# MCU.net
KiCad netlist of a schematic drawn in Altium Designer
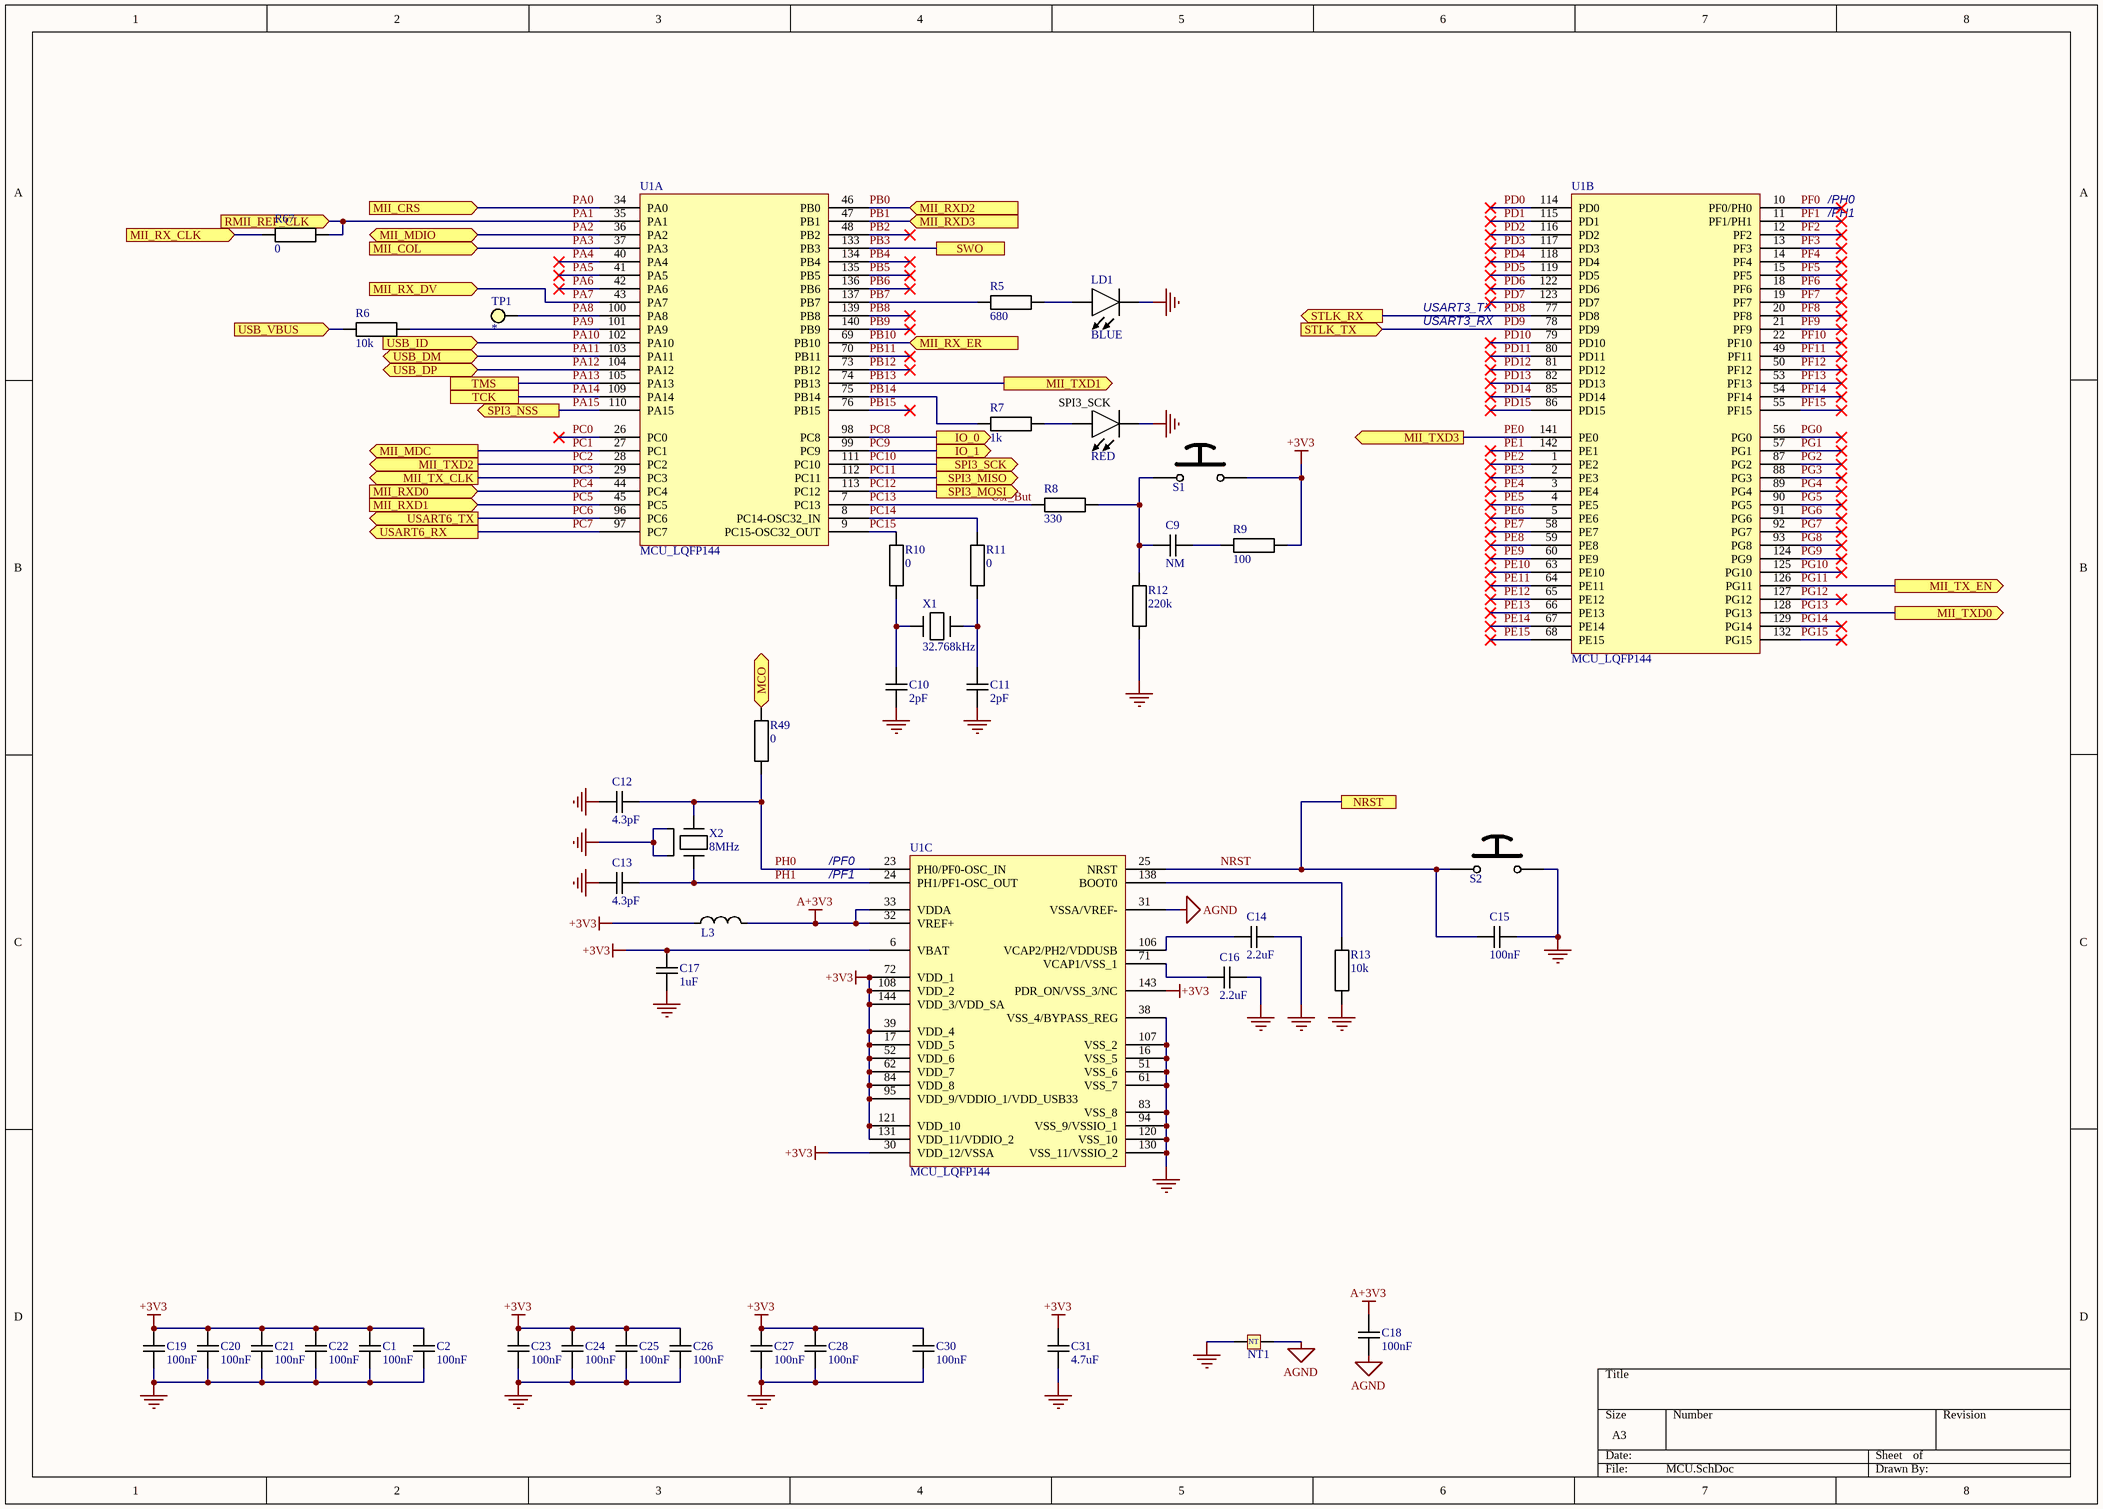
[diagram p0: MCU.SchDoc]

(export (version "E")
  (design (tool "Eeschema 10.0.6"))
  (components
    (comp (ref "C1")
      (value "100nF")
      (footprint "CAPACITOR 1608 REFLOW")
      (description "Capacitor")
      (libsource (lib "Capacitor") (part "Capacitor"))
    )
    (comp (ref "C2")
      (value "100nF")
      (footprint "CAPACITOR 1608 REFLOW")
      (description "Capacitor")
      (libsource (lib "Capacitor") (part "Capacitor"))
    )
    (comp (ref "C9")
      (value "NM")
      (footprint "CAPACITOR 1608 REFLOW")
      (description "Capacitor")
      (libsource (lib "Capacitor") (part "Capacitor"))
    )
    (comp (ref "C10")
      (value "2pF")
      (footprint "CAPACITOR 1608 REFLOW")
      (description "Capacitor")
      (libsource (lib "Capacitor") (part "Capacitor"))
    )
    (comp (ref "C11")
      (value "2pF")
      (footprint "CAPACITOR 1608 REFLOW")
      (description "Capacitor")
      (libsource (lib "Capacitor") (part "Capacitor"))
    )
    (comp (ref "C12")
      (value "4.3pF")
      (footprint "CAPACITOR 1608 REFLOW")
      (description "Capacitor")
      (libsource (lib "Capacitor") (part "Capacitor"))
    )
    (comp (ref "C13")
      (value "4.3pF")
      (footprint "CAPACITOR 1608 REFLOW")
      (description "Capacitor")
      (libsource (lib "Capacitor") (part "Capacitor"))
    )
    (comp (ref "C14")
      (value "2.2uF")
      (footprint "CAPACITOR 1608 REFLOW")
      (description "Capacitor")
      (libsource (lib "Capacitor") (part "Capacitor"))
    )
    (comp (ref "C15")
      (value "100nF")
      (footprint "CAPACITOR 1608 REFLOW")
      (description "Capacitor")
      (libsource (lib "Capacitor") (part "Capacitor"))
    )
    (comp (ref "C16")
      (value "2.2uF")
      (footprint "CAPACITOR 1608 REFLOW")
      (description "Capacitor")
      (libsource (lib "Capacitor") (part "Capacitor"))
    )
    (comp (ref "C17")
      (value "1uF")
      (footprint "CAPACITOR 1608 REFLOW")
      (description "Capacitor")
      (libsource (lib "Capacitor") (part "Capacitor"))
    )
    (comp (ref "C18")
      (value "100nF")
      (footprint "CAPACITOR 1608 REFLOW")
      (description "Capacitor")
      (libsource (lib "Capacitor") (part "Capacitor"))
    )
    (comp (ref "C19")
      (value "100nF")
      (footprint "CAPACITOR 1608 REFLOW")
      (description "Capacitor")
      (libsource (lib "Capacitor") (part "Capacitor"))
    )
    (comp (ref "C20")
      (value "100nF")
      (footprint "CAPACITOR 1608 REFLOW")
      (description "Capacitor")
      (libsource (lib "Capacitor") (part "Capacitor"))
    )
    (comp (ref "C21")
      (value "100nF")
      (footprint "CAPACITOR 1608 REFLOW")
      (description "Capacitor")
      (libsource (lib "Capacitor") (part "Capacitor"))
    )
    (comp (ref "C22")
      (value "100nF")
      (footprint "CAPACITOR 1608 REFLOW")
      (description "Capacitor")
      (libsource (lib "Capacitor") (part "Capacitor"))
    )
    (comp (ref "C23")
      (value "100nF")
      (footprint "CAPACITOR 1608 REFLOW")
      (description "Capacitor")
      (libsource (lib "Capacitor") (part "Capacitor"))
    )
    (comp (ref "C24")
      (value "100nF")
      (footprint "CAPACITOR 1608 REFLOW")
      (description "Capacitor")
      (libsource (lib "Capacitor") (part "Capacitor"))
    )
    (comp (ref "C25")
      (value "100nF")
      (footprint "CAPACITOR 1608 REFLOW")
      (description "Capacitor")
      (libsource (lib "Capacitor") (part "Capacitor"))
    )
    (comp (ref "C26")
      (value "100nF")
      (footprint "CAPACITOR 1608 REFLOW")
      (description "Capacitor")
      (libsource (lib "Capacitor") (part "Capacitor"))
    )
    (comp (ref "C27")
      (value "100nF")
      (footprint "CAPACITOR 1608 REFLOW")
      (description "Capacitor")
      (libsource (lib "Capacitor") (part "Capacitor"))
    )
    (comp (ref "C28")
      (value "100nF")
      (footprint "CAPACITOR 1608 REFLOW")
      (description "Capacitor")
      (libsource (lib "Capacitor") (part "Capacitor"))
    )
    (comp (ref "C30")
      (value "100nF")
      (footprint "CAPACITOR 1608 REFLOW")
      (description "Capacitor")
      (libsource (lib "Capacitor") (part "Capacitor"))
    )
    (comp (ref "C31")
      (value "4.7uF")
      (footprint "CAPACITOR 1608 REFLOW")
      (description "Capacitor")
      (libsource (lib "Capacitor") (part "Capacitor"))
    )
    (comp (ref "L3")
      (value "*")
      (footprint "INDUCTOR 1608 REFLOW")
      (description "Inductor")
      (libsource (lib "Inductor") (part "Inductor"))
    )
    (comp (ref "LD1")
      (value "BLUE")
      (footprint "LED 1608 REFLOW")
      (description "LED generic")
      (libsource (lib "Diode") (part "LED"))
    )
    (comp (ref "LD2")
      (value "RED")
      (footprint "LED 1608 REFLOW")
      (description "LED generic")
      (libsource (lib "Diode") (part "LED"))
    )
    (comp (ref "NT1")
      (value "Net Tie")
      (footprint "NET TIE 1005")
      (description "Connection for 2 different NETNAME")
      (libsource (lib "Jumper") (part "Net Tie"))
    )
    (comp (ref "R5")
      (value "680")
      (footprint "RESISTOR 1608 REFLOW")
      (description "Resistor")
      (libsource (lib "Resistor") (part "Resistor"))
    )
    (comp (ref "R6")
      (value "10k")
      (footprint "RESISTOR 1608 REFLOW")
      (description "Resistor")
      (libsource (lib "Resistor") (part "Resistor"))
    )
    (comp (ref "R7")
      (value "1k")
      (footprint "RESISTOR 1608 REFLOW")
      (description "Resistor")
      (libsource (lib "Resistor") (part "Resistor"))
    )
    (comp (ref "R8")
      (value "330")
      (footprint "RESISTOR 1608 REFLOW")
      (description "Resistor")
      (libsource (lib "Resistor") (part "Resistor"))
    )
    (comp (ref "R9")
      (value "100")
      (footprint "RESISTOR 1608 REFLOW")
      (description "Resistor")
      (libsource (lib "Resistor") (part "Resistor"))
    )
    (comp (ref "R10")
      (value "0")
      (footprint "RESISTOR 1608 REFLOW")
      (description "Resistor")
      (libsource (lib "Resistor") (part "Resistor"))
    )
    (comp (ref "R11")
      (value "0")
      (footprint "RESISTOR 1608 REFLOW")
      (description "Resistor")
      (libsource (lib "Resistor") (part "Resistor"))
    )
    (comp (ref "R12")
      (value "220k")
      (footprint "RESISTOR 1608 REFLOW")
      (description "Resistor")
      (libsource (lib "Resistor") (part "Resistor"))
    )
    (comp (ref "R13")
      (value "10k")
      (footprint "RESISTOR 1608 REFLOW")
      (description "Resistor")
      (libsource (lib "Resistor") (part "Resistor"))
    )
    (comp (ref "R49")
      (value "0")
      (footprint "RESISTOR 1608 REFLOW")
      (description "Resistor")
      (libsource (lib "Resistor") (part "Resistor"))
    )
    (comp (ref "R67")
      (value "0")
      (footprint "RESISTOR 1608 REFLOW")
      (description "Resistor")
      (libsource (lib "Resistor") (part "Resistor"))
    )
    (comp (ref "S1")
      (value "*")
      (footprint "Push Button C2.5X3.0 OMRON B3U-1000P(M)-B")
      (description "Push Button, 2 pins")
      (libsource (lib "Button") (part "Push Button 2Pins"))
    )
    (comp (ref "S2")
      (value "*")
      (footprint "Push Button C2.5X3.0 OMRON B3U-1000P(M)-B")
      (description "Push Button, 2 pins")
      (libsource (lib "Button") (part "Push Button 2Pins"))
    )
    (comp (ref "TP1")
      (value "*")
      (footprint "Pad D0.8")
      (description "Pad")
      (libsource (lib "Testpoint") (part "Pad"))
    )
    (comp (ref "U1")
      (value "MCU_LQFP144")
      (footprint "LQFP144 P0.5 C20.0x20.0 H1.6")
      (libsource (lib "MB1137") (part "MCU_LQFP144"))
    )
    (comp (ref "X1")
      (value "32.768kHz")
      (footprint "Crystal C2.0x1.2 CTS TF20")
      (description "Crystal C2.0x1.2 CTS TF20")
      (libsource (lib "Oscillator") (part "Crystal C2.0x1.2 CTS TF20"))
    )
    (comp (ref "X2")
      (value "8MHz")
      (footprint "Crystal C2.0x1.6 Abracon ABM11W")
      (description "Crystal C2.0x1.6 Abracon ABM11W")
      (libsource (lib "Oscillator") (part "Crystal C2.0x1.6 Abracon ABM11W"))
    )
  )
  (nets
    (net (code "1") (name "+3V3") (class "Default")
      (node (ref "C1") (pin "1") (pinfunction "1_1") (pintype "passive"))
      (node (ref "C17") (pin "2") (pinfunction "2_2") (pintype "passive"))
      (node (ref "C19") (pin "1") (pinfunction "1_1") (pintype "passive"))
      (node (ref "C2") (pin "1") (pinfunction "1_1") (pintype "passive"))
      (node (ref "C20") (pin "1") (pinfunction "1_1") (pintype "passive"))
      (node (ref "C21") (pin "1") (pinfunction "1_1") (pintype "passive"))
      (node (ref "C22") (pin "1") (pinfunction "1_1") (pintype "passive"))
      (node (ref "C23") (pin "1") (pinfunction "1_1") (pintype "passive"))
      (node (ref "C24") (pin "1") (pinfunction "1_1") (pintype "passive"))
      (node (ref "C25") (pin "1") (pinfunction "1_1") (pintype "passive"))
      (node (ref "C26") (pin "1") (pinfunction "1_1") (pintype "passive"))
      (node (ref "C27") (pin "1") (pinfunction "1_1") (pintype "passive"))
      (node (ref "C28") (pin "1") (pinfunction "1_1") (pintype "passive"))
      (node (ref "C30") (pin "1") (pinfunction "1_1") (pintype "passive"))
      (node (ref "C31") (pin "1") (pinfunction "1_1") (pintype "passive"))
      (node (ref "L3") (pin "1") (pinfunction "1_1") (pintype "passive"))
      (node (ref "R9") (pin "2") (pinfunction "2_2") (pintype "passive"))
      (node (ref "S1") (pin "2") (pinfunction "2_2") (pintype "passive"))
      (node (ref "U1") (pin "108") (pinfunction "VDD_2_108") (pintype "passive"))
      (node (ref "U1") (pin "121") (pinfunction "VDD_10_121") (pintype "passive"))
      (node (ref "U1") (pin "131") (pinfunction "VDD_11/VDDIO_2_131") (pintype "passive"))
      (node (ref "U1") (pin "143") (pinfunction "PDR_ON/VSS_3/NC_143") (pintype "passive"))
      (node (ref "U1") (pin "144") (pinfunction "VDD_3/VDD_SA_144") (pintype "passive"))
      (node (ref "U1") (pin "17") (pinfunction "VDD_5_17") (pintype "passive"))
      (node (ref "U1") (pin "30") (pinfunction "VDD_12/VSSA_30") (pintype "passive"))
      (node (ref "U1") (pin "39") (pinfunction "VDD_4_39") (pintype "passive"))
      (node (ref "U1") (pin "52") (pinfunction "VDD_6_52") (pintype "passive"))
      (node (ref "U1") (pin "6") (pinfunction "VBAT_6") (pintype "passive"))
      (node (ref "U1") (pin "62") (pinfunction "VDD_7_62") (pintype "passive"))
      (node (ref "U1") (pin "72") (pinfunction "VDD_1_72") (pintype "passive"))
      (node (ref "U1") (pin "84") (pinfunction "VDD_8_84") (pintype "passive"))
      (node (ref "U1") (pin "95") (pinfunction "VDD_9/VDDIO_1/VDD_USB33_95") (pintype "passive"))
    )
    (net (code "2") (name "/MCO") (class "Default")
      (node (ref "R49") (pin "1") (pinfunction "1_1") (pintype "passive"))
    )
    (net (code "3") (name "/MII_RX_CLK") (class "Default")
      (node (ref "R67") (pin "1") (pinfunction "1_1") (pintype "passive"))
    )
    (net (code "4") (name "/NRST") (class "Default")
      (node (ref "C15") (pin "2") (pinfunction "2_2") (pintype "passive"))
      (node (ref "S2") (pin "1") (pinfunction "1_1") (pintype "passive"))
      (node (ref "U1") (pin "25") (pinfunction "NRST_25") (pintype "passive"))
    )
    (net (code "5") (name "/PA0") (class "Default")
      (node (ref "U1") (pin "34") (pinfunction "PA0_34") (pintype "passive"))
    )
    (net (code "6") (name "/PA1") (class "Default")
      (node (ref "R67") (pin "2") (pinfunction "2_2") (pintype "passive"))
      (node (ref "U1") (pin "35") (pinfunction "PA1_35") (pintype "passive"))
    )
    (net (code "7") (name "/PA2") (class "Default")
      (node (ref "U1") (pin "36") (pinfunction "PA2_36") (pintype "passive"))
    )
    (net (code "8") (name "/PA3") (class "Default")
      (node (ref "U1") (pin "37") (pinfunction "PA3_37") (pintype "passive"))
    )
    (net (code "9") (name "/PA4") (class "Default")
      (node (ref "U1") (pin "40") (pinfunction "PA4_40") (pintype "passive+no_connect"))
    )
    (net (code "10") (name "/PA5") (class "Default")
      (node (ref "U1") (pin "41") (pinfunction "PA5_41") (pintype "passive+no_connect"))
    )
    (net (code "11") (name "/PA6") (class "Default")
      (node (ref "U1") (pin "42") (pinfunction "PA6_42") (pintype "passive+no_connect"))
    )
    (net (code "12") (name "/PA7") (class "Default")
      (node (ref "U1") (pin "43") (pinfunction "PA7_43") (pintype "passive"))
    )
    (net (code "13") (name "/PA8") (class "Default")
      (node (ref "TP1") (pin "1") (pinfunction "1_1") (pintype "passive"))
      (node (ref "U1") (pin "100") (pinfunction "PA8_100") (pintype "passive"))
    )
    (net (code "14") (name "/PA9") (class "Default")
      (node (ref "R6") (pin "1") (pinfunction "1_1") (pintype "passive"))
      (node (ref "U1") (pin "101") (pinfunction "PA9_101") (pintype "passive"))
    )
    (net (code "15") (name "/PA10") (class "Default")
      (node (ref "U1") (pin "102") (pinfunction "PA10_102") (pintype "passive"))
    )
    (net (code "16") (name "/PA11") (class "Default")
      (node (ref "U1") (pin "103") (pinfunction "PA11_103") (pintype "passive"))
    )
    (net (code "17") (name "/PA12") (class "Default")
      (node (ref "U1") (pin "104") (pinfunction "PA12_104") (pintype "passive"))
    )
    (net (code "18") (name "/PA13") (class "Default")
      (node (ref "U1") (pin "105") (pinfunction "PA13_105") (pintype "passive"))
    )
    (net (code "19") (name "/PA14") (class "Default")
      (node (ref "U1") (pin "109") (pinfunction "PA14_109") (pintype "passive"))
    )
    (net (code "20") (name "/PA15") (class "Default")
      (node (ref "U1") (pin "110") (pinfunction "PA15_110") (pintype "passive"))
    )
    (net (code "21") (name "/PB0") (class "Default")
      (node (ref "U1") (pin "46") (pinfunction "PB0_46") (pintype "passive"))
    )
    (net (code "22") (name "/PB1") (class "Default")
      (node (ref "U1") (pin "47") (pinfunction "PB1_47") (pintype "passive"))
    )
    (net (code "23") (name "/PB2") (class "Default")
      (node (ref "U1") (pin "48") (pinfunction "PB2_48") (pintype "passive+no_connect"))
    )
    (net (code "24") (name "/PB3") (class "Default")
      (node (ref "U1") (pin "133") (pinfunction "PB3_133") (pintype "passive"))
    )
    (net (code "25") (name "/PB4") (class "Default")
      (node (ref "U1") (pin "134") (pinfunction "PB4_134") (pintype "passive+no_connect"))
    )
    (net (code "26") (name "/PB5") (class "Default")
      (node (ref "U1") (pin "135") (pinfunction "PB5_135") (pintype "passive+no_connect"))
    )
    (net (code "27") (name "/PB6") (class "Default")
      (node (ref "U1") (pin "136") (pinfunction "PB6_136") (pintype "passive+no_connect"))
    )
    (net (code "28") (name "/PB7") (class "Default")
      (node (ref "R5") (pin "2") (pinfunction "2_2") (pintype "passive"))
      (node (ref "U1") (pin "137") (pinfunction "PB7_137") (pintype "passive"))
    )
    (net (code "29") (name "/PB8") (class "Default")
      (node (ref "U1") (pin "139") (pinfunction "PB8_139") (pintype "passive+no_connect"))
    )
    (net (code "30") (name "/PB9") (class "Default")
      (node (ref "U1") (pin "140") (pinfunction "PB9_140") (pintype "passive+no_connect"))
    )
    (net (code "31") (name "/PB10") (class "Default")
      (node (ref "U1") (pin "69") (pinfunction "PB10_69") (pintype "passive"))
    )
    (net (code "32") (name "/PB11") (class "Default")
      (node (ref "U1") (pin "70") (pinfunction "PB11_70") (pintype "passive+no_connect"))
    )
    (net (code "33") (name "/PB12") (class "Default")
      (node (ref "U1") (pin "73") (pinfunction "PB12_73") (pintype "passive+no_connect"))
    )
    (net (code "34") (name "/PB13") (class "Default")
      (node (ref "U1") (pin "74") (pinfunction "PB13_74") (pintype "passive"))
    )
    (net (code "35") (name "/PB14") (class "Default")
      (node (ref "R7") (pin "2") (pinfunction "2_2") (pintype "passive"))
      (node (ref "U1") (pin "75") (pinfunction "PB14_75") (pintype "passive"))
    )
    (net (code "36") (name "/PB15") (class "Default")
      (node (ref "U1") (pin "76") (pinfunction "PB15_76") (pintype "passive+no_connect"))
    )
    (net (code "37") (name "/PC0") (class "Default")
      (node (ref "U1") (pin "26") (pinfunction "PC0_26") (pintype "passive+no_connect"))
    )
    (net (code "38") (name "/PC1") (class "Default")
      (node (ref "U1") (pin "27") (pinfunction "PC1_27") (pintype "passive"))
    )
    (net (code "39") (name "/PC2") (class "Default")
      (node (ref "U1") (pin "28") (pinfunction "PC2_28") (pintype "passive"))
    )
    (net (code "40") (name "/PC3") (class "Default")
      (node (ref "U1") (pin "29") (pinfunction "PC3_29") (pintype "passive"))
    )
    (net (code "41") (name "/PC4") (class "Default")
      (node (ref "U1") (pin "44") (pinfunction "PC4_44") (pintype "passive"))
    )
    (net (code "42") (name "/PC5") (class "Default")
      (node (ref "U1") (pin "45") (pinfunction "PC5_45") (pintype "passive"))
    )
    (net (code "43") (name "/PC6") (class "Default")
      (node (ref "U1") (pin "96") (pinfunction "PC6_96") (pintype "passive"))
    )
    (net (code "44") (name "/PC7") (class "Default")
      (node (ref "U1") (pin "97") (pinfunction "PC7_97") (pintype "passive"))
    )
    (net (code "45") (name "/PC8") (class "Default")
      (node (ref "U1") (pin "98") (pinfunction "PC8_98") (pintype "passive"))
    )
    (net (code "46") (name "/PC9") (class "Default")
      (node (ref "U1") (pin "99") (pinfunction "PC9_99") (pintype "passive"))
    )
    (net (code "47") (name "/PC10") (class "Default")
      (node (ref "U1") (pin "111") (pinfunction "PC10_111") (pintype "passive"))
    )
    (net (code "48") (name "/PC11") (class "Default")
      (node (ref "U1") (pin "112") (pinfunction "PC11_112") (pintype "passive"))
    )
    (net (code "49") (name "/PC12") (class "Default")
      (node (ref "U1") (pin "113") (pinfunction "PC12_113") (pintype "passive"))
    )
    (net (code "50") (name "/PC13") (class "Default")
      (node (ref "R8") (pin "1") (pinfunction "1_1") (pintype "passive"))
      (node (ref "U1") (pin "7") (pinfunction "PC13_7") (pintype "passive"))
    )
    (net (code "51") (name "/PC14") (class "Default")
      (node (ref "R11") (pin "2") (pinfunction "2_2") (pintype "passive"))
      (node (ref "U1") (pin "8") (pinfunction "PC14-OSC32_IN_8") (pintype "passive"))
    )
    (net (code "52") (name "/PC15") (class "Default")
      (node (ref "R10") (pin "1") (pinfunction "1_1") (pintype "passive"))
      (node (ref "U1") (pin "9") (pinfunction "PC15-OSC32_OUT_9") (pintype "passive"))
    )
    (net (code "53") (name "/PD0") (class "Default")
      (node (ref "U1") (pin "114") (pinfunction "PD0_114") (pintype "passive+no_connect"))
    )
    (net (code "54") (name "/PD1") (class "Default")
      (node (ref "U1") (pin "115") (pinfunction "PD1_115") (pintype "passive+no_connect"))
    )
    (net (code "55") (name "/PD2") (class "Default")
      (node (ref "U1") (pin "116") (pinfunction "PD2_116") (pintype "passive+no_connect"))
    )
    (net (code "56") (name "/PD3") (class "Default")
      (node (ref "U1") (pin "117") (pinfunction "PD3_117") (pintype "passive+no_connect"))
    )
    (net (code "57") (name "/PD4") (class "Default")
      (node (ref "U1") (pin "118") (pinfunction "PD4_118") (pintype "passive+no_connect"))
    )
    (net (code "58") (name "/PD5") (class "Default")
      (node (ref "U1") (pin "119") (pinfunction "PD5_119") (pintype "passive+no_connect"))
    )
    (net (code "59") (name "/PD6") (class "Default")
      (node (ref "U1") (pin "122") (pinfunction "PD6_122") (pintype "passive+no_connect"))
    )
    (net (code "60") (name "/PD7") (class "Default")
      (node (ref "U1") (pin "123") (pinfunction "PD7_123") (pintype "passive+no_connect"))
    )
    (net (code "61") (name "/PD8") (class "Default")
      (node (ref "U1") (pin "77") (pinfunction "PD8_77") (pintype "passive"))
    )
    (net (code "62") (name "/PD9") (class "Default")
      (node (ref "U1") (pin "78") (pinfunction "PD9_78") (pintype "passive"))
    )
    (net (code "63") (name "/PD10") (class "Default")
      (node (ref "U1") (pin "79") (pinfunction "PD10_79") (pintype "passive+no_connect"))
    )
    (net (code "64") (name "/PD11") (class "Default")
      (node (ref "U1") (pin "80") (pinfunction "PD11_80") (pintype "passive+no_connect"))
    )
    (net (code "65") (name "/PD12") (class "Default")
      (node (ref "U1") (pin "81") (pinfunction "PD12_81") (pintype "passive+no_connect"))
    )
    (net (code "66") (name "/PD13") (class "Default")
      (node (ref "U1") (pin "82") (pinfunction "PD13_82") (pintype "passive+no_connect"))
    )
    (net (code "67") (name "/PD14") (class "Default")
      (node (ref "U1") (pin "85") (pinfunction "PD14_85") (pintype "passive+no_connect"))
    )
    (net (code "68") (name "/PD15") (class "Default")
      (node (ref "U1") (pin "86") (pinfunction "PD15_86") (pintype "passive+no_connect"))
    )
    (net (code "69") (name "/PE0") (class "Default")
      (node (ref "U1") (pin "141") (pinfunction "PE0_141") (pintype "passive"))
    )
    (net (code "70") (name "/PE1") (class "Default")
      (node (ref "U1") (pin "142") (pinfunction "PE1_142") (pintype "passive+no_connect"))
    )
    (net (code "71") (name "/PE2") (class "Default")
      (node (ref "U1") (pin "1") (pinfunction "PE2_1") (pintype "passive+no_connect"))
    )
    (net (code "72") (name "/PE3") (class "Default")
      (node (ref "U1") (pin "2") (pinfunction "PE3_2") (pintype "passive+no_connect"))
    )
    (net (code "73") (name "/PE4") (class "Default")
      (node (ref "U1") (pin "3") (pinfunction "PE4_3") (pintype "passive+no_connect"))
    )
    (net (code "74") (name "/PE5") (class "Default")
      (node (ref "U1") (pin "4") (pinfunction "PE5_4") (pintype "passive+no_connect"))
    )
    (net (code "75") (name "/PE6") (class "Default")
      (node (ref "U1") (pin "5") (pinfunction "PE6_5") (pintype "passive+no_connect"))
    )
    (net (code "76") (name "/PE7") (class "Default")
      (node (ref "U1") (pin "58") (pinfunction "PE7_58") (pintype "passive+no_connect"))
    )
    (net (code "77") (name "/PE8") (class "Default")
      (node (ref "U1") (pin "59") (pinfunction "PE8_59") (pintype "passive+no_connect"))
    )
    (net (code "78") (name "/PE9") (class "Default")
      (node (ref "U1") (pin "60") (pinfunction "PE9_60") (pintype "passive+no_connect"))
    )
    (net (code "79") (name "/PE10") (class "Default")
      (node (ref "U1") (pin "63") (pinfunction "PE10_63") (pintype "passive+no_connect"))
    )
    (net (code "80") (name "/PE11") (class "Default")
      (node (ref "U1") (pin "64") (pinfunction "PE11_64") (pintype "passive+no_connect"))
    )
    (net (code "81") (name "/PE12") (class "Default")
      (node (ref "U1") (pin "65") (pinfunction "PE12_65") (pintype "passive+no_connect"))
    )
    (net (code "82") (name "/PE13") (class "Default")
      (node (ref "U1") (pin "66") (pinfunction "PE13_66") (pintype "passive+no_connect"))
    )
    (net (code "83") (name "/PE14") (class "Default")
      (node (ref "U1") (pin "67") (pinfunction "PE14_67") (pintype "passive+no_connect"))
    )
    (net (code "84") (name "/PE15") (class "Default")
      (node (ref "U1") (pin "68") (pinfunction "PE15_68") (pintype "passive+no_connect"))
    )
    (net (code "85") (name "/PF0") (class "Default")
      (node (ref "U1") (pin "10") (pinfunction "PF0/PH0_10") (pintype "passive+no_connect"))
    )
    (net (code "86") (name "/PF1") (class "Default")
      (node (ref "U1") (pin "11") (pinfunction "PF1/PH1_11") (pintype "passive+no_connect"))
    )
    (net (code "87") (name "/PF2") (class "Default")
      (node (ref "U1") (pin "12") (pinfunction "PF2_12") (pintype "passive+no_connect"))
    )
    (net (code "88") (name "/PF3") (class "Default")
      (node (ref "U1") (pin "13") (pinfunction "PF3_13") (pintype "passive+no_connect"))
    )
    (net (code "89") (name "/PF4") (class "Default")
      (node (ref "U1") (pin "14") (pinfunction "PF4_14") (pintype "passive+no_connect"))
    )
    (net (code "90") (name "/PF5") (class "Default")
      (node (ref "U1") (pin "15") (pinfunction "PF5_15") (pintype "passive+no_connect"))
    )
    (net (code "91") (name "/PF6") (class "Default")
      (node (ref "U1") (pin "18") (pinfunction "PF6_18") (pintype "passive+no_connect"))
    )
    (net (code "92") (name "/PF7") (class "Default")
      (node (ref "U1") (pin "19") (pinfunction "PF7_19") (pintype "passive+no_connect"))
    )
    (net (code "93") (name "/PF8") (class "Default")
      (node (ref "U1") (pin "20") (pinfunction "PF8_20") (pintype "passive+no_connect"))
    )
    (net (code "94") (name "/PF9") (class "Default")
      (node (ref "U1") (pin "21") (pinfunction "PF9_21") (pintype "passive+no_connect"))
    )
    (net (code "95") (name "/PF10") (class "Default")
      (node (ref "U1") (pin "22") (pinfunction "PF10_22") (pintype "passive+no_connect"))
    )
    (net (code "96") (name "/PF11") (class "Default")
      (node (ref "U1") (pin "49") (pinfunction "PF11_49") (pintype "passive+no_connect"))
    )
    (net (code "97") (name "/PF12") (class "Default")
      (node (ref "U1") (pin "50") (pinfunction "PF12_50") (pintype "passive+no_connect"))
    )
    (net (code "98") (name "/PF13") (class "Default")
      (node (ref "U1") (pin "53") (pinfunction "PF13_53") (pintype "passive+no_connect"))
    )
    (net (code "99") (name "/PF14") (class "Default")
      (node (ref "U1") (pin "54") (pinfunction "PF14_54") (pintype "passive+no_connect"))
    )
    (net (code "100") (name "/PF15") (class "Default")
      (node (ref "U1") (pin "55") (pinfunction "PF15_55") (pintype "passive+no_connect"))
    )
    (net (code "101") (name "/PG0") (class "Default")
      (node (ref "U1") (pin "56") (pinfunction "PG0_56") (pintype "passive+no_connect"))
    )
    (net (code "102") (name "/PG1") (class "Default")
      (node (ref "U1") (pin "57") (pinfunction "PG1_57") (pintype "passive+no_connect"))
    )
    (net (code "103") (name "/PG2") (class "Default")
      (node (ref "U1") (pin "87") (pinfunction "PG2_87") (pintype "passive+no_connect"))
    )
    (net (code "104") (name "/PG3") (class "Default")
      (node (ref "U1") (pin "88") (pinfunction "PG3_88") (pintype "passive+no_connect"))
    )
    (net (code "105") (name "/PG4") (class "Default")
      (node (ref "U1") (pin "89") (pinfunction "PG4_89") (pintype "passive+no_connect"))
    )
    (net (code "106") (name "/PG5") (class "Default")
      (node (ref "U1") (pin "90") (pinfunction "PG5_90") (pintype "passive+no_connect"))
    )
    (net (code "107") (name "/PG6") (class "Default")
      (node (ref "U1") (pin "91") (pinfunction "PG6_91") (pintype "passive+no_connect"))
    )
    (net (code "108") (name "/PG7") (class "Default")
      (node (ref "U1") (pin "92") (pinfunction "PG7_92") (pintype "passive+no_connect"))
    )
    (net (code "109") (name "/PG8") (class "Default")
      (node (ref "U1") (pin "93") (pinfunction "PG8_93") (pintype "passive+no_connect"))
    )
    (net (code "110") (name "/PG9") (class "Default")
      (node (ref "U1") (pin "124") (pinfunction "PG9_124") (pintype "passive+no_connect"))
    )
    (net (code "111") (name "/PG10") (class "Default")
      (node (ref "U1") (pin "125") (pinfunction "PG10_125") (pintype "passive+no_connect"))
    )
    (net (code "112") (name "/PG11") (class "Default")
      (node (ref "U1") (pin "126") (pinfunction "PG11_126") (pintype "passive"))
    )
    (net (code "113") (name "/PG12") (class "Default")
      (node (ref "U1") (pin "127") (pinfunction "PG12_127") (pintype "passive+no_connect"))
    )
    (net (code "114") (name "/PG13") (class "Default")
      (node (ref "U1") (pin "128") (pinfunction "PG13_128") (pintype "passive"))
    )
    (net (code "115") (name "/PG14") (class "Default")
      (node (ref "U1") (pin "129") (pinfunction "PG14_129") (pintype "passive+no_connect"))
    )
    (net (code "116") (name "/PG15") (class "Default")
      (node (ref "U1") (pin "132") (pinfunction "PG15_132") (pintype "passive+no_connect"))
    )
    (net (code "117") (name "/PH0") (class "Default")
      (node (ref "C12") (pin "1") (pinfunction "1_1") (pintype "passive"))
      (node (ref "R49") (pin "2") (pinfunction "2_2") (pintype "passive"))
      (node (ref "U1") (pin "23") (pinfunction "PH0/PF0-OSC_IN_23") (pintype "passive"))
      (node (ref "X2") (pin "1") (pinfunction "1_1") (pintype "passive"))
    )
    (net (code "118") (name "/PH1") (class "Default")
      (node (ref "C13") (pin "1") (pinfunction "1_1") (pintype "passive"))
      (node (ref "U1") (pin "24") (pinfunction "PH1/PF1-OSC_OUT_24") (pintype "passive"))
      (node (ref "X2") (pin "3") (pinfunction "3_3") (pintype "passive"))
    )
    (net (code "119") (name "/USB_VBUS") (class "Default")
      (node (ref "R6") (pin "2") (pinfunction "2_2") (pintype "passive"))
    )
    (net (code "120") (name "A+3V3") (class "Default")
      (node (ref "C18") (pin "1") (pinfunction "1_1") (pintype "passive"))
      (node (ref "L3") (pin "2") (pinfunction "2_2") (pintype "passive"))
      (node (ref "U1") (pin "32") (pinfunction "VREF+_32") (pintype "passive"))
      (node (ref "U1") (pin "33") (pinfunction "VDDA_33") (pintype "passive"))
    )
    (net (code "121") (name "AGND") (class "Default")
      (node (ref "C18") (pin "2") (pinfunction "2_2") (pintype "passive"))
      (node (ref "NT1") (pin "2") (pinfunction "2_2") (pintype "passive"))
      (node (ref "U1") (pin "31") (pinfunction "VSSA/VREF-_31") (pintype "passive"))
    )
    (net (code "122") (name "GND") (class "Default")
      (node (ref "C1") (pin "2") (pinfunction "2_2") (pintype "passive"))
      (node (ref "C10") (pin "1") (pinfunction "1_1") (pintype "passive"))
      (node (ref "C11") (pin "1") (pinfunction "1_1") (pintype "passive"))
      (node (ref "C12") (pin "2") (pinfunction "2_2") (pintype "passive"))
      (node (ref "C13") (pin "2") (pinfunction "2_2") (pintype "passive"))
      (node (ref "C14") (pin "2") (pinfunction "2_2") (pintype "passive"))
      (node (ref "C15") (pin "1") (pinfunction "1_1") (pintype "passive"))
      (node (ref "C16") (pin "2") (pinfunction "2_2") (pintype "passive"))
      (node (ref "C17") (pin "1") (pinfunction "1_1") (pintype "passive"))
      (node (ref "C19") (pin "2") (pinfunction "2_2") (pintype "passive"))
      (node (ref "C2") (pin "2") (pinfunction "2_2") (pintype "passive"))
      (node (ref "C20") (pin "2") (pinfunction "2_2") (pintype "passive"))
      (node (ref "C21") (pin "2") (pinfunction "2_2") (pintype "passive"))
      (node (ref "C22") (pin "2") (pinfunction "2_2") (pintype "passive"))
      (node (ref "C23") (pin "2") (pinfunction "2_2") (pintype "passive"))
      (node (ref "C24") (pin "2") (pinfunction "2_2") (pintype "passive"))
      (node (ref "C25") (pin "2") (pinfunction "2_2") (pintype "passive"))
      (node (ref "C26") (pin "2") (pinfunction "2_2") (pintype "passive"))
      (node (ref "C27") (pin "2") (pinfunction "2_2") (pintype "passive"))
      (node (ref "C28") (pin "2") (pinfunction "2_2") (pintype "passive"))
      (node (ref "C30") (pin "2") (pinfunction "2_2") (pintype "passive"))
      (node (ref "C31") (pin "2") (pinfunction "2_2") (pintype "passive"))
      (node (ref "LD1") (pin "1") (pinfunction "C_1") (pintype "passive"))
      (node (ref "LD2") (pin "1") (pinfunction "C_1") (pintype "passive"))
      (node (ref "NT1") (pin "1") (pinfunction "1_1") (pintype "passive"))
      (node (ref "R12") (pin "2") (pinfunction "2_2") (pintype "passive"))
      (node (ref "R13") (pin "2") (pinfunction "2_2") (pintype "passive"))
      (node (ref "S2") (pin "2") (pinfunction "2_2") (pintype "passive"))
      (node (ref "U1") (pin "107") (pinfunction "VSS_2_107") (pintype "passive"))
      (node (ref "U1") (pin "120") (pinfunction "VSS_10_120") (pintype "passive"))
      (node (ref "U1") (pin "130") (pinfunction "VSS_11/VSSIO_2_130") (pintype "passive"))
      (node (ref "U1") (pin "16") (pinfunction "VSS_5_16") (pintype "passive"))
      (node (ref "U1") (pin "38") (pinfunction "VSS_4/BYPASS_REG_38") (pintype "passive"))
      (node (ref "U1") (pin "51") (pinfunction "VSS_6_51") (pintype "passive"))
      (node (ref "U1") (pin "61") (pinfunction "VSS_7_61") (pintype "passive"))
      (node (ref "U1") (pin "83") (pinfunction "VSS_8_83") (pintype "passive"))
      (node (ref "U1") (pin "94") (pinfunction "VSS_9/VSSIO_1_94") (pintype "passive"))
      (node (ref "X2") (pin "2") (pinfunction "2_2") (pintype "passive"))
      (node (ref "X2") (pin "4") (pinfunction "4_4") (pintype "passive"))
    )
    (net (code "123") (name "Net-(C9-Pad1)") (class "Default")
      (node (ref "C9") (pin "1") (pinfunction "1_1") (pintype "passive"))
      (node (ref "R9") (pin "1") (pinfunction "1_1") (pintype "passive"))
    )
    (net (code "124") (name "Net-(C9-Pad2)") (class "Default")
      (node (ref "C9") (pin "2") (pinfunction "2_2") (pintype "passive"))
      (node (ref "R12") (pin "1") (pinfunction "1_1") (pintype "passive"))
      (node (ref "R8") (pin "2") (pinfunction "2_2") (pintype "passive"))
      (node (ref "S1") (pin "1") (pinfunction "1_1") (pintype "passive"))
    )
    (net (code "125") (name "Net-(C10-Pad2)") (class "Default")
      (node (ref "C10") (pin "2") (pinfunction "2_2") (pintype "passive"))
      (node (ref "R10") (pin "2") (pinfunction "2_2") (pintype "passive"))
      (node (ref "X1") (pin "1") (pinfunction "1_1") (pintype "passive"))
    )
    (net (code "126") (name "Net-(C11-Pad2)") (class "Default")
      (node (ref "C11") (pin "2") (pinfunction "2_2") (pintype "passive"))
      (node (ref "R11") (pin "1") (pinfunction "1_1") (pintype "passive"))
      (node (ref "X1") (pin "2") (pinfunction "2_2") (pintype "passive"))
    )
    (net (code "127") (name "Net-(LD1-A)") (class "Default")
      (node (ref "LD1") (pin "2") (pinfunction "A_2") (pintype "passive"))
      (node (ref "R5") (pin "1") (pinfunction "1_1") (pintype "passive"))
    )
    (net (code "128") (name "Net-(LD2-A)") (class "Default")
      (node (ref "LD2") (pin "2") (pinfunction "A_2") (pintype "passive"))
      (node (ref "R7") (pin "1") (pinfunction "1_1") (pintype "passive"))
    )
    (net (code "129") (name "Net-(U1C-BOOT0)") (class "Default")
      (node (ref "R13") (pin "1") (pinfunction "1_1") (pintype "passive"))
      (node (ref "U1") (pin "138") (pinfunction "BOOT0_138") (pintype "passive"))
    )
    (net (code "130") (name "Net-(U1C-VCAP1{slash}VSS_1)") (class "Default")
      (node (ref "C16") (pin "1") (pinfunction "1_1") (pintype "passive"))
      (node (ref "U1") (pin "71") (pinfunction "VCAP1/VSS_1_71") (pintype "passive"))
    )
    (net (code "131") (name "Net-(U1C-VCAP2{slash}PH2{slash}VDDUSB)") (class "Default")
      (node (ref "C14") (pin "1") (pinfunction "1_1") (pintype "passive"))
      (node (ref "U1") (pin "106") (pinfunction "VCAP2/PH2/VDDUSB_106") (pintype "passive"))
    )
  )
)
